# 16-DDR4_ECC_AND_TERMINATIONS.net
KiCad netlist of a schematic drawn in Altium Designer
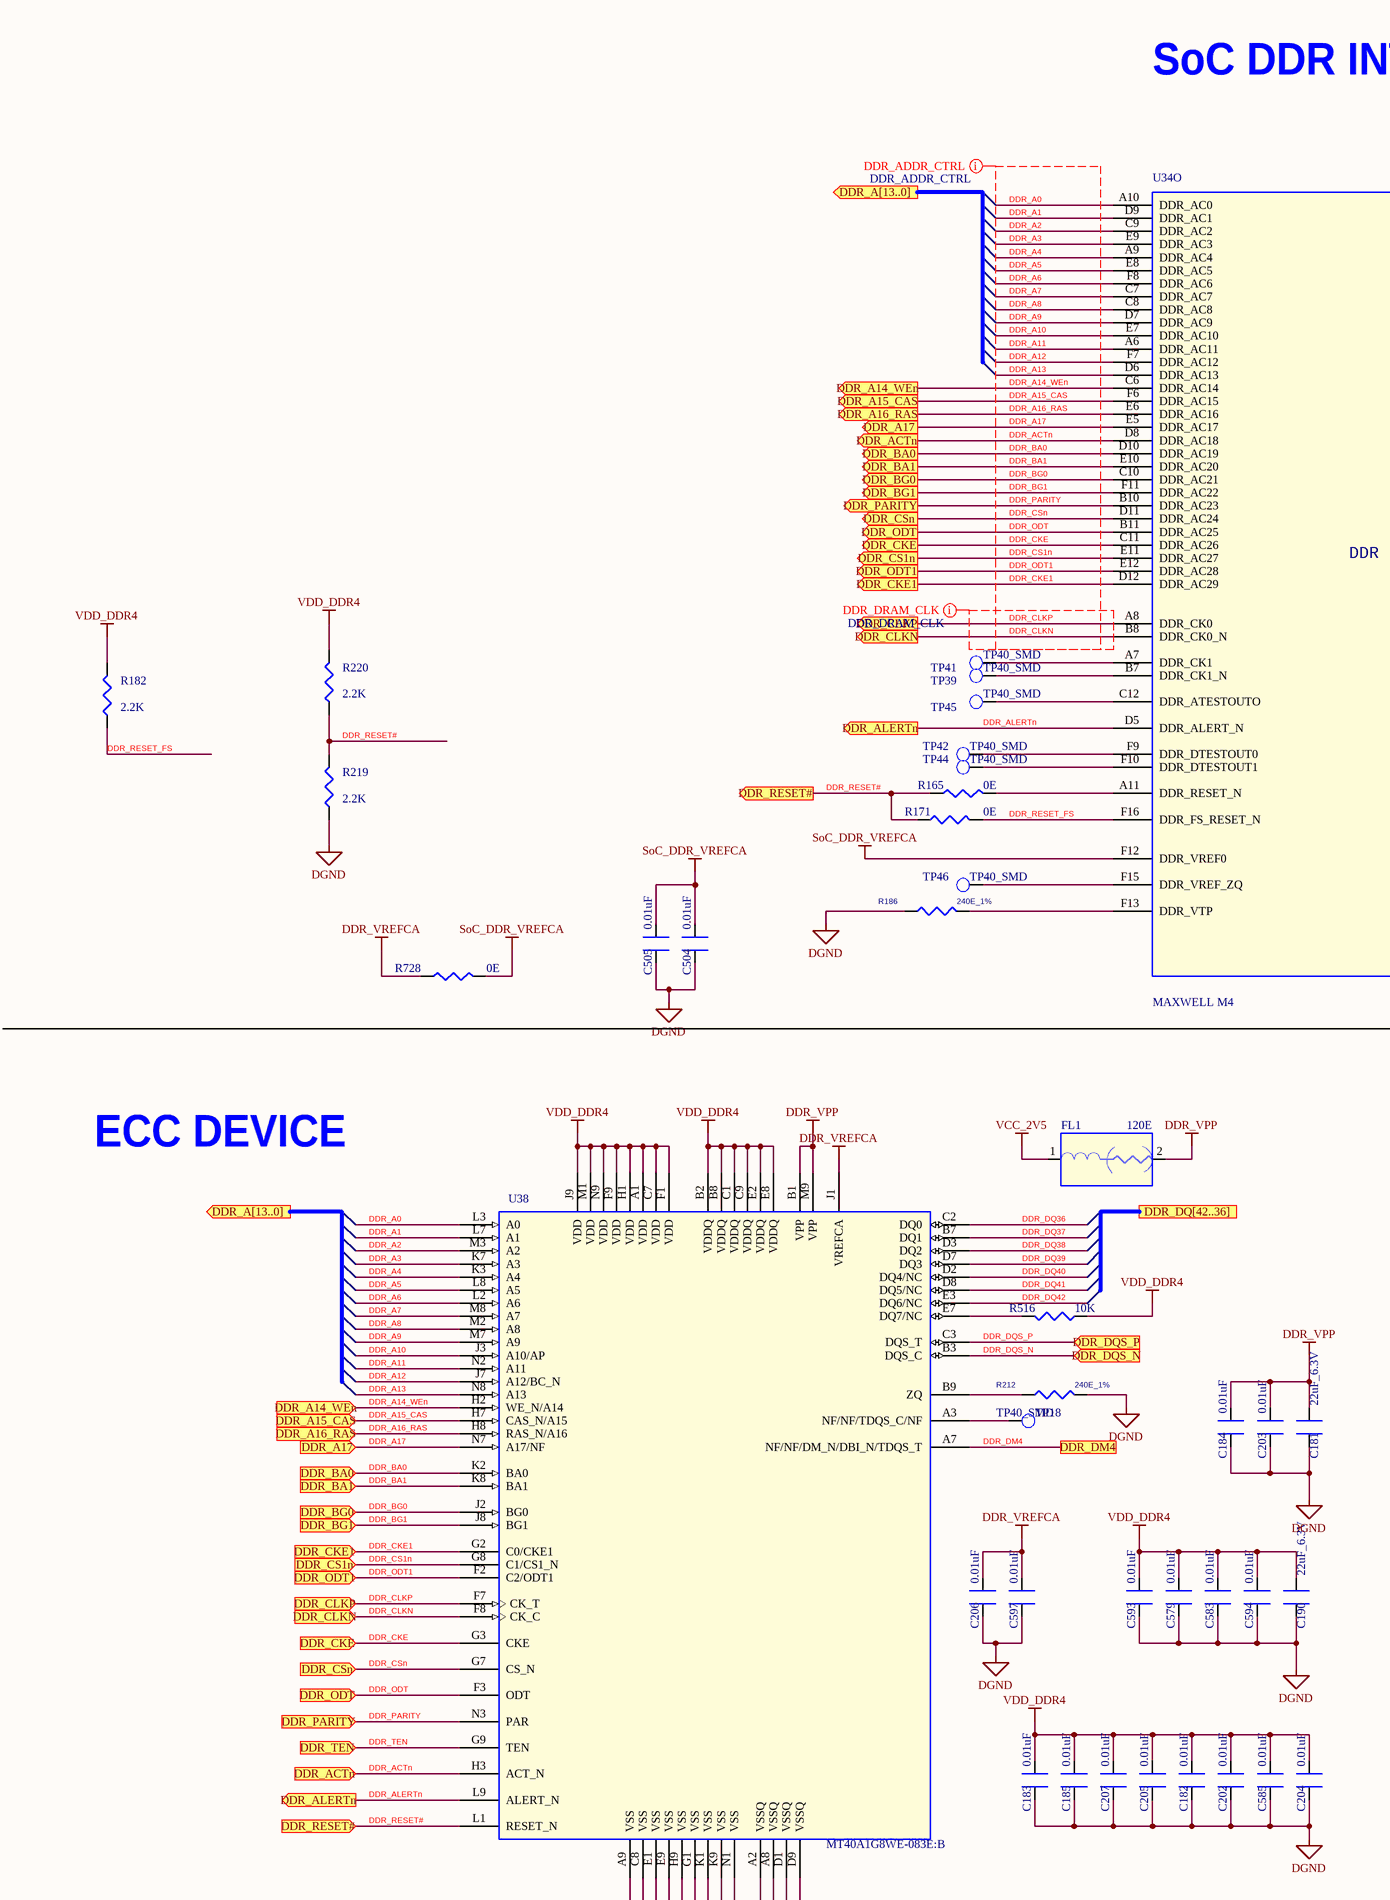
[diagram p0: 16-DDR4 ECC AND TERMINATIONS.SchDoc, top left]
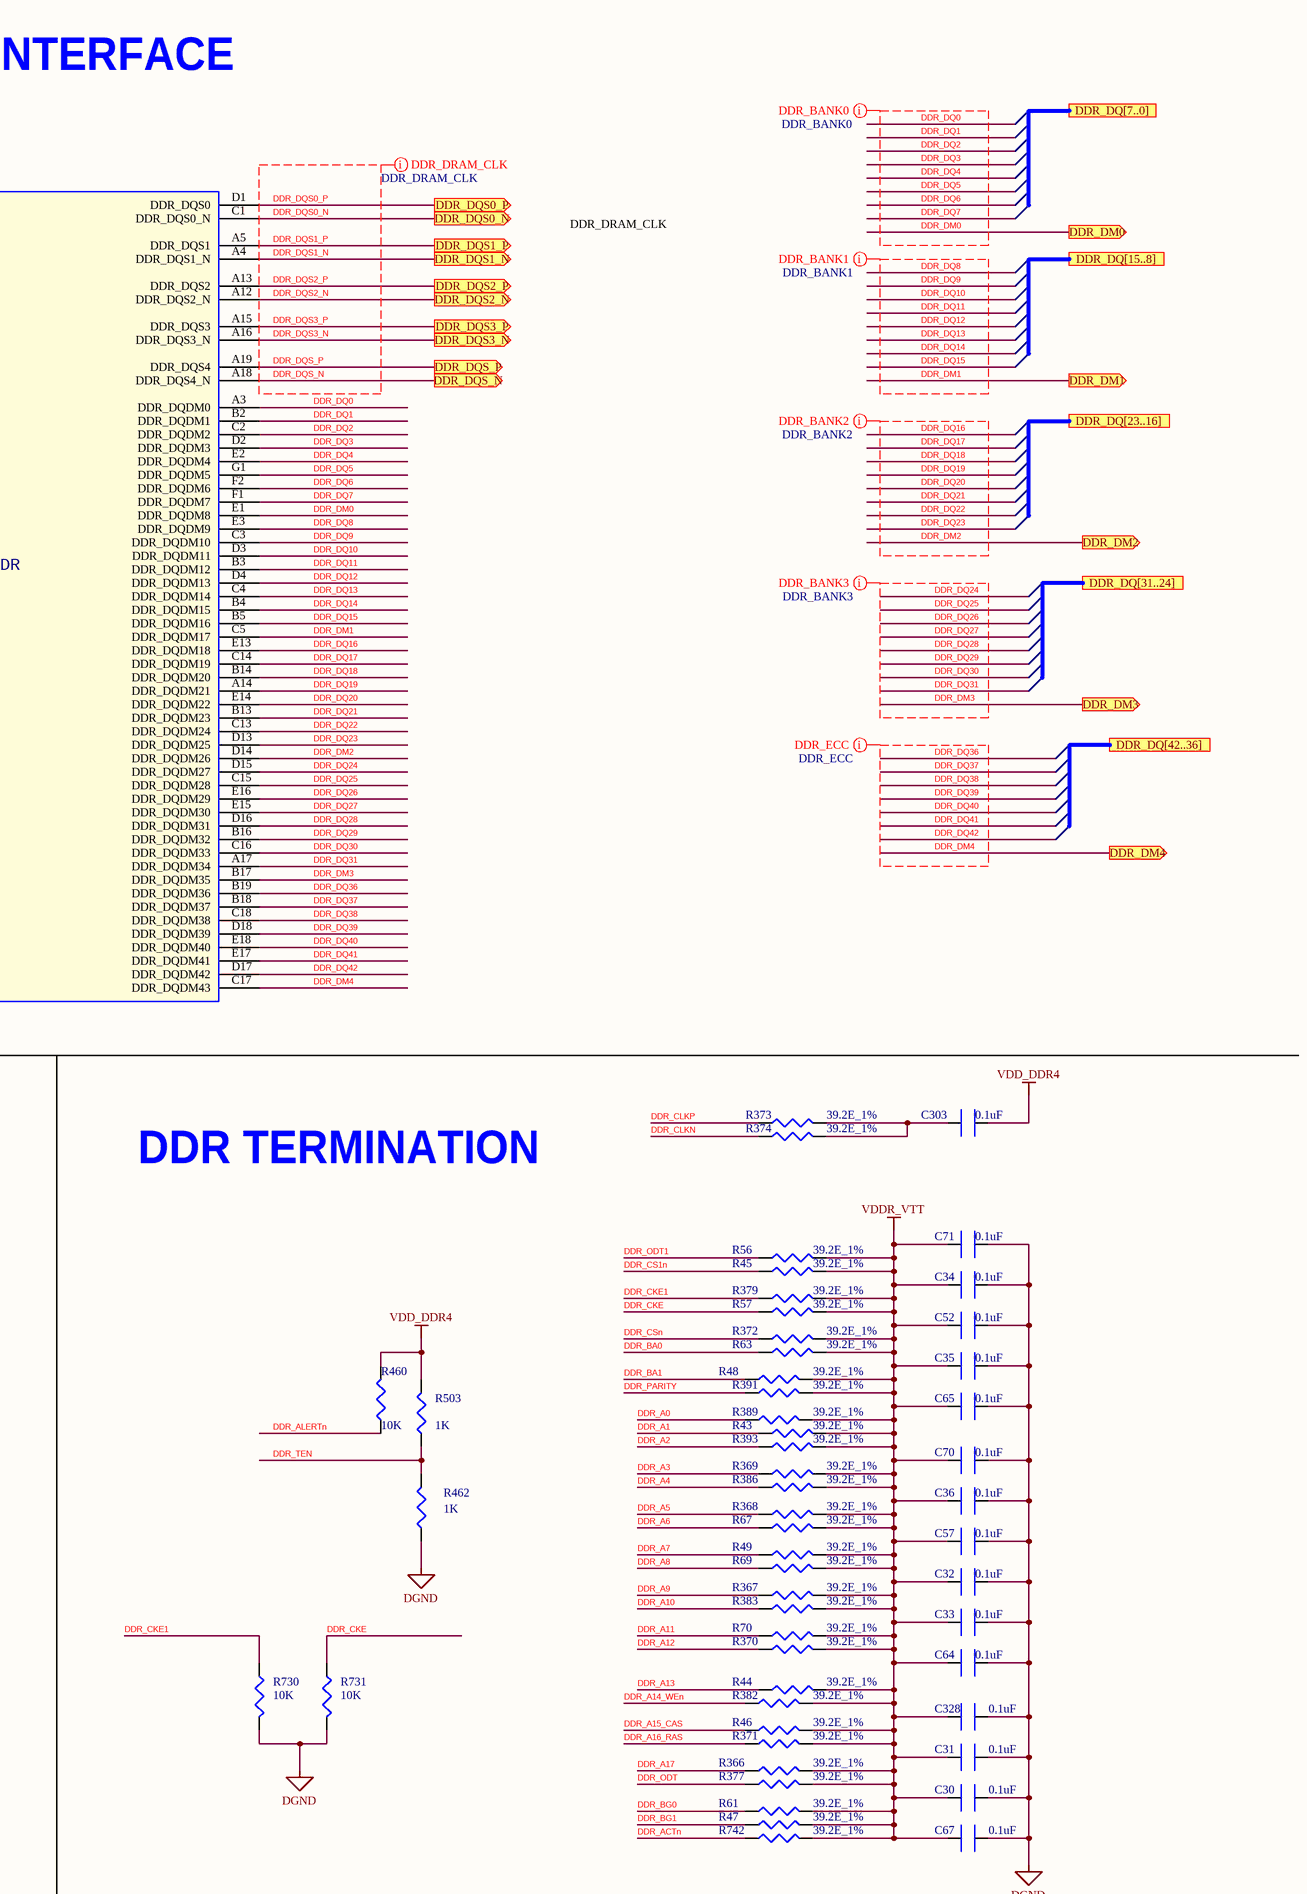
[diagram p1: 16-DDR4 ECC AND TERMINATIONS.SchDoc, top right]
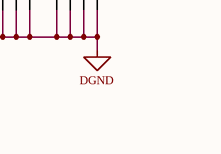
[diagram p2: 16-DDR4 ECC AND TERMINATIONS.SchDoc, bottom left]
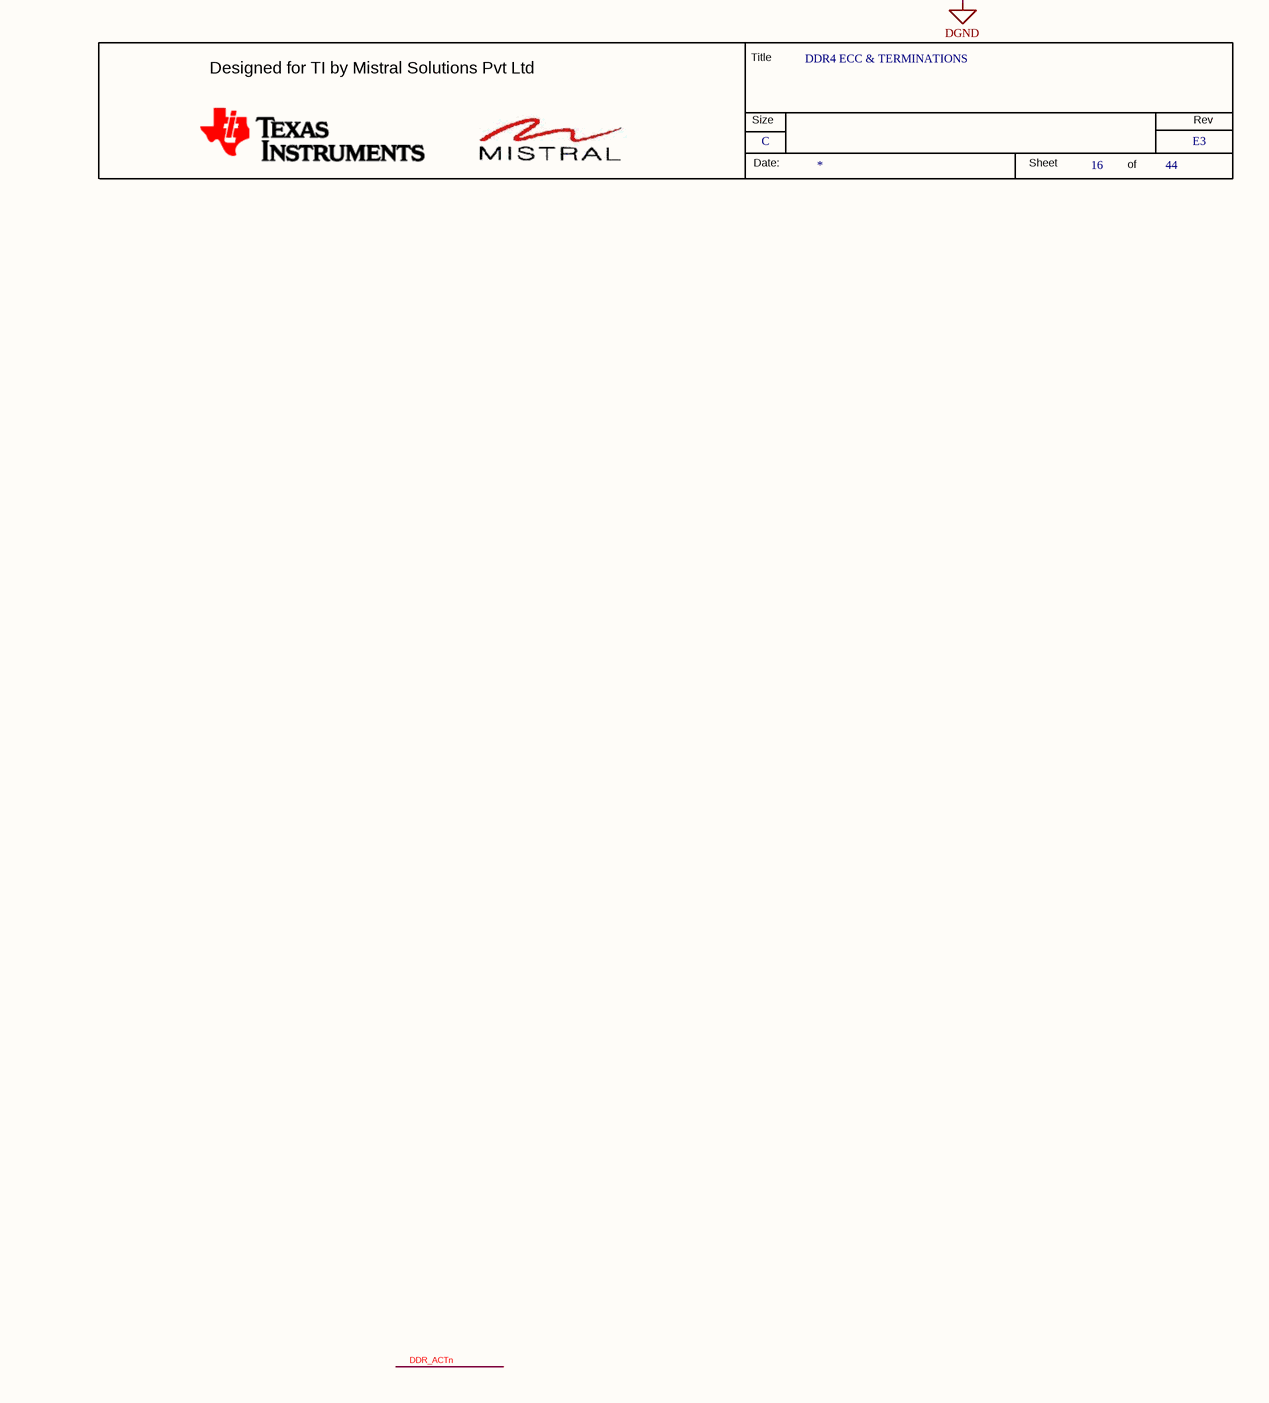
[diagram p3: 16-DDR4 ECC AND TERMINATIONS.SchDoc, bottom right]

(export (version "E")
  (design (tool "Eeschema 10.0.6"))
  (components
    (comp (ref "C30")
      (value "0.1uF")
      (footprint "TMDX654GPEVM_BRD:CAP0201_0-5")
      (description "CAP CERAMIC 0.1uF 16V 10% X5R 0201")
      (fields
        (field (name "MISTRAL PART NO") "120009030072-R")
        (field (name "MFR_PART_NUMBER") "GRM033R61C104KE84J")
      )
      (libsource (lib "*") (part "CAP_Dup3"))
    )
    (comp (ref "C31")
      (value "0.1uF")
      (footprint "TMDX654GPEVM_BRD:CAP0201_0-5")
      (description "CAP CERAMIC 0.1uF 16V 10% X5R 0201")
      (fields (field (name "DISTRIBUTOR_PART_NUMBER") "490-16742-1-ND") (field (name "VOLTAGE") "16V"))
      (libsource (lib "*") (part "CAP_Dup3"))
    )
    (comp (ref "C32")
      (value "0.1uF")
      (footprint "TMDX654GPEVM_BRD:CAP0201_0-5")
      (description "CAP CERAMIC 0.1uF 16V 10% X5R 0201")
      (fields
        (field (name "MISTRAL PART NO") "120009030072-R")
        (field (name "MFR_PART_NUMBER") "GRM033R61C104KE84J")
      )
      (libsource (lib "*") (part "CAP_Dup3"))
    )
    (comp (ref "C33")
      (value "0.1uF")
      (footprint "TMDX654GPEVM_BRD:CAP0201_0-5")
      (description "CAP CERAMIC 0.1uF 16V 10% X5R 0201")
      (fields
        (field (name "MISTRAL PART NO") "120009030072-R")
        (field (name "MFR_PART_NUMBER") "GRM033R61C104KE84J")
      )
      (libsource (lib "*") (part "CAP_Dup3"))
    )
    (comp (ref "C34")
      (value "0.1uF")
      (footprint "TMDX654GPEVM_BRD:CAP0201_0-5")
      (description "CAP CERAMIC 0.1uF 16V 10% X5R 0201")
      (fields
        (field (name "MISTRAL PART NO") "120009030072-R")
        (field (name "MFR_PART_NUMBER") "GRM033R61C104KE84J")
      )
      (libsource (lib "*") (part "CAP_Dup3"))
    )
    (comp (ref "C35")
      (value "0.1uF")
      (footprint "TMDX654GPEVM_BRD:CAP0201_0-5")
      (description "CAP CERAMIC 0.1uF 16V 10% X5R 0201")
      (fields (field (name "DISTRIBUTOR_PART_NUMBER") "490-16742-1-ND") (field (name "VOLTAGE") "16V"))
      (libsource (lib "*") (part "CAP_Dup3"))
    )
    (comp (ref "C36")
      (value "0.1uF")
      (footprint "TMDX654GPEVM_BRD:CAP0201_0-5")
      (description "CAP CERAMIC 0.1uF 16V 10% X5R 0201")
      (fields
        (field (name "MISTRAL PART NO") "120009030072-R")
        (field (name "MFR_PART_NUMBER") "GRM033R61C104KE84J")
      )
      (libsource (lib "*") (part "CAP_Dup3"))
    )
    (comp (ref "C52")
      (value "0.1uF")
      (footprint "TMDX654GPEVM_BRD:CAP0201_0-5")
      (description "CAP CERAMIC 0.1uF 16V 10% X5R 0201")
      (fields
        (field (name "MISTRAL PART NO") "120009030072-R")
        (field (name "MFR_PART_NUMBER") "GRM033R61C104KE84J")
      )
      (libsource (lib "*") (part "CAP_Dup3"))
    )
    (comp (ref "C57")
      (value "0.1uF")
      (footprint "TMDX654GPEVM_BRD:CAP0201_0-5")
      (description "CAP CERAMIC 0.1uF 16V 10% X5R 0201")
      (fields
        (field (name "MISTRAL PART NO") "120009030072-R")
        (field (name "MFR_PART_NUMBER") "GRM033R61C104KE84J")
      )
      (libsource (lib "*") (part "CAP_Dup3"))
    )
    (comp (ref "C64")
      (value "0.1uF")
      (footprint "TMDX654GPEVM_BRD:CAP0201_0-5")
      (description "CAP CERAMIC 0.1uF 16V 10% X5R 0201")
      (fields
        (field (name "MISTRAL PART NO") "120009030072-R")
        (field (name "MFR_PART_NUMBER") "GRM033R61C104KE84J")
      )
      (libsource (lib "*") (part "CAP_Dup3"))
    )
    (comp (ref "C65")
      (value "0.1uF")
      (footprint "TMDX654GPEVM_BRD:CAP0201_0-5")
      (description "CAP CERAMIC 0.1uF 16V 10% X5R 0201")
      (fields
        (field (name "MISTRAL PART NO") "120009030072-R")
        (field (name "MFR_PART_NUMBER") "GRM033R61C104KE84J")
      )
      (libsource (lib "*") (part "CAP_Dup3"))
    )
    (comp (ref "C67")
      (value "0.1uF")
      (footprint "TMDX654GPEVM_BRD:CAP0201_0-5")
      (description "CAP CERAMIC 0.1uF 16V 10% X5R 0201")
      (fields
        (field (name "MISTRAL PART NO") "120009030072-R")
        (field (name "MFR_PART_NUMBER") "GRM033R61C104KE84J")
      )
      (libsource (lib "*") (part "CAP_Dup3"))
    )
    (comp (ref "C70")
      (value "0.1uF")
      (footprint "TMDX654GPEVM_BRD:CAP0201_0-5")
      (description "CAP CERAMIC 0.1uF 16V 10% X5R 0201")
      (fields
        (field (name "MISTRAL PART NO") "120009030072-R")
        (field (name "MFR_PART_NUMBER") "GRM033R61C104KE84J")
      )
      (libsource (lib "*") (part "CAP_Dup3"))
    )
    (comp (ref "C71")
      (value "0.1uF")
      (footprint "TMDX654GPEVM_BRD:CAP0201_0-5")
      (description "CAP CERAMIC 0.1uF 16V 10% X5R 0201")
      (fields
        (field (name "MISTRAL PART NO") "120009030072-R")
        (field (name "MFR_PART_NUMBER") "GRM033R61C104KE84J")
      )
      (libsource (lib "*") (part "CAP_Dup3"))
    )
    (comp (ref "C181")
      (value "22uF_6.3V")
      (footprint "TMDX654GPEVM_BRD:CAP0603")
      (description "CAP CERAMIC 22uF 6.3V 20% X5R 0603")
      (fields
        (field (name "MISTRAL PART NO") "120015090007-R")
        (field (name "MFR_PART_NUMBER") "GRM188R60J226MEA0")
      )
      (libsource (lib "*") (part "CAP_Dup3"))
    )
    (comp (ref "C182")
      (value "0.01uF")
      (footprint "TMDX654GPEVM_BRD:CAP0201_0-5")
      (description "CAP CERAMIC 0.01uF 25V 10% X5R 0201")
      (fields (field (name "DISTRIBUTOR_PART_NUMBER") "GRM033R61E103KA12J-ND") (field (name "VOLTAGE") "25V"))
      (libsource (lib "*") (part "CAP_Dup3"))
    )
    (comp (ref "C183")
      (value "0.01uF")
      (footprint "TMDX654GPEVM_BRD:CAP0201_0-5")
      (description "CAP CERAMIC 0.01uF 25V 10% X5R 0201")
      (fields (field (name "DISTRIBUTOR_PART_NUMBER") "GRM033R61E103KA12J-ND") (field (name "VOLTAGE") "25V"))
      (libsource (lib "*") (part "CAP_Dup3"))
    )
    (comp (ref "C184")
      (value "0.01uF")
      (footprint "TMDX654GPEVM_BRD:CAP0201_0-5")
      (description "CAP CERAMIC 0.01uF 25V 10% X5R 0201")
      (fields (field (name "DISTRIBUTOR_PART_NUMBER") "GRM033R61E103KA12J-ND") (field (name "VOLTAGE") "25V"))
      (libsource (lib "*") (part "CAP_Dup3"))
    )
    (comp (ref "C185")
      (value "0.01uF")
      (footprint "TMDX654GPEVM_BRD:CAP0201_0-5")
      (description "CAP CERAMIC 0.01uF 25V 10% X5R 0201")
      (fields (field (name "DISTRIBUTOR_PART_NUMBER") "GRM033R61E103KA12J-ND") (field (name "VOLTAGE") "25V"))
      (libsource (lib "*") (part "CAP_Dup3"))
    )
    (comp (ref "C190")
      (value "22uF_6.3V")
      (footprint "TMDX654GPEVM_BRD:CAP0603")
      (description "CAP CERAMIC 22uF 6.3V 20% X5R 0603")
      (fields
        (field (name "MISTRAL PART NO") "120015090007-R")
        (field (name "MFR_PART_NUMBER") "GRM188R60J226MEA0")
      )
      (libsource (lib "*") (part "CAP_Dup3"))
    )
    (comp (ref "C202")
      (value "0.01uF")
      (footprint "TMDX654GPEVM_BRD:CAP0201_0-5")
      (description "CAP CERAMIC 0.01uF 25V 10% X5R 0201")
      (fields (field (name "DISTRIBUTOR_PART_NUMBER") "GRM033R61E103KA12J-ND") (field (name "VOLTAGE") "25V"))
      (libsource (lib "*") (part "CAP_Dup3"))
    )
    (comp (ref "C203")
      (value "0.01uF")
      (footprint "TMDX654GPEVM_BRD:CAP0201_0-5")
      (description "CAP CERAMIC 0.01uF 25V 10% X5R 0201")
      (fields (field (name "DISTRIBUTOR_PART_NUMBER") "GRM033R61E103KA12J-ND") (field (name "VOLTAGE") "25V"))
      (libsource (lib "*") (part "CAP_Dup3"))
    )
    (comp (ref "C204")
      (value "0.01uF")
      (footprint "TMDX654GPEVM_BRD:CAP0201_0-5")
      (description "CAP CERAMIC 0.01uF 25V 10% X5R 0201")
      (fields
        (field (name "MISTRAL PART NO") "120018010007-R")
        (field (name "MFR_PART_NUMBER") "GRM033R61E103KA12J")
      )
      (libsource (lib "*") (part "CAP_Dup3"))
    )
    (comp (ref "C205")
      (value "0.01uF")
      (footprint "TMDX654GPEVM_BRD:CAP0201_0-5")
      (description "CAP CERAMIC 0.01uF 25V 10% X5R 0201")
      (fields (field (name "DISTRIBUTOR_PART_NUMBER") "GRM033R61E103KA12J-ND") (field (name "VOLTAGE") "25V"))
      (libsource (lib "*") (part "CAP_Dup3"))
    )
    (comp (ref "C206")
      (value "0.01uF")
      (footprint "TMDX654GPEVM_BRD:CAP0201_0-5")
      (description "CAP CERAMIC 0.01uF 25V 10% X5R 0201")
      (fields (field (name "DISTRIBUTOR_PART_NUMBER") "GRM033R61E103KA12J-ND") (field (name "VOLTAGE") "25V"))
      (libsource (lib "*") (part "CAP_Dup3"))
    )
    (comp (ref "C207")
      (value "0.01uF")
      (footprint "TMDX654GPEVM_BRD:CAP0201_0-5")
      (description "CAP CERAMIC 0.01uF 25V 10% X5R 0201")
      (fields (field (name "DISTRIBUTOR_PART_NUMBER") "GRM033R61E103KA12J-ND") (field (name "VOLTAGE") "25V"))
      (libsource (lib "*") (part "CAP_Dup3"))
    )
    (comp (ref "C303")
      (value "0.1uF")
      (footprint "TMDX654GPEVM_BRD:CAP0201_0-5")
      (description "CAP CERAMIC 0.1uF 16V 10% X5R 0201")
      (fields (field (name "DISTRIBUTOR_PART_NUMBER") "490-16742-1-ND") (field (name "VOLTAGE") "16V"))
      (libsource (lib "*") (part "CAP_Dup3"))
    )
    (comp (ref "C328")
      (value "0.1uF")
      (footprint "TMDX654GPEVM_BRD:CAP0201_0-5")
      (description "CAP CERAMIC 0.1uF 16V 10% X5R 0201")
      (fields
        (field (name "MISTRAL PART NO") "120009030072-R")
        (field (name "MFR_PART_NUMBER") "GRM033R61C104KE84J")
      )
      (libsource (lib "*") (part "CAP_Dup3"))
    )
    (comp (ref "C504")
      (value "0.01uF")
      (footprint "TMDX654GPEVM_BRD:CAP0201_0-5")
      (description "CAP CERAMIC 0.01uF 25V 10% X5R 0201")
      (fields (field (name "DISTRIBUTOR_PART_NUMBER") "GRM033R61E103KA12J-ND") (field (name "VOLTAGE") "25V"))
      (libsource (lib "*") (part "CAP_Dup3"))
    )
    (comp (ref "C505")
      (value "0.01uF")
      (footprint "TMDX654GPEVM_BRD:CAP0201_0-5")
      (description "CAP CERAMIC 0.01uF 25V 10% X5R 0201")
      (fields (field (name "DISTRIBUTOR_PART_NUMBER") "GRM033R61E103KA12J-ND") (field (name "VOLTAGE") "25V"))
      (libsource (lib "*") (part "CAP_Dup3"))
    )
    (comp (ref "C579")
      (value "0.01uF")
      (footprint "TMDX654GPEVM_BRD:CAP0201_0-5")
      (description "CAP CERAMIC 0.01uF 25V 10% X5R 0201")
      (fields (field (name "DISTRIBUTOR_PART_NUMBER") "GRM033R61E103KA12J-ND") (field (name "VOLTAGE") "25V"))
      (libsource (lib "*") (part "CAP_Dup3"))
    )
    (comp (ref "C583")
      (value "0.01uF")
      (footprint "TMDX654GPEVM_BRD:CAP0201_0-5")
      (description "CAP CERAMIC 0.01uF 25V 10% X5R 0201")
      (fields (field (name "DISTRIBUTOR_PART_NUMBER") "GRM033R61E103KA12J-ND") (field (name "VOLTAGE") "25V"))
      (libsource (lib "*") (part "CAP_Dup3"))
    )
    (comp (ref "C585")
      (value "0.01uF")
      (footprint "TMDX654GPEVM_BRD:CAP0201_0-5")
      (description "CAP CERAMIC 0.01uF 25V 10% X5R 0201")
      (fields (field (name "DISTRIBUTOR_PART_NUMBER") "GRM033R61E103KA12J-ND") (field (name "VOLTAGE") "25V"))
      (libsource (lib "*") (part "CAP_Dup3"))
    )
    (comp (ref "C593")
      (value "0.01uF")
      (footprint "TMDX654GPEVM_BRD:CAP0201_0-5")
      (description "CAP CERAMIC 0.01uF 25V 10% X5R 0201")
      (fields (field (name "DISTRIBUTOR_PART_NUMBER") "GRM033R61E103KA12J-ND") (field (name "VOLTAGE") "25V"))
      (libsource (lib "*") (part "CAP_Dup3"))
    )
    (comp (ref "C594")
      (value "0.01uF")
      (footprint "TMDX654GPEVM_BRD:CAP0201_0-5")
      (description "CAP CERAMIC 0.01uF 25V 10% X5R 0201")
      (fields (field (name "DISTRIBUTOR_PART_NUMBER") "GRM033R61E103KA12J-ND") (field (name "VOLTAGE") "25V"))
      (libsource (lib "*") (part "CAP_Dup3"))
    )
    (comp (ref "C597")
      (value "0.01uF")
      (footprint "TMDX654GPEVM_BRD:CAP0201_0-5")
      (description "CAP CERAMIC 0.01uF 25V 10% X5R 0201")
      (fields (field (name "DISTRIBUTOR_PART_NUMBER") "GRM033R61E103KA12J-ND") (field (name "VOLTAGE") "25V"))
      (libsource (lib "*") (part "CAP_Dup3"))
    )
    (comp (ref "FL1")
      (value "120E")
      (footprint "EMIFIL_BLM15A_0402_0-6")
      (description "FERRITE CHIP 120E 1.3A 0402")
      (fields
        (field (name "MISTRAL PART NO") "130012030043-R")
        (field (name "MFR_PART_NUMBER") "BLM15PD121SN1")
      )
      (libsource (lib "*") (part "EMIFILTER_IND"))
    )
    (comp (ref "R43")
      (value "39.2E_1%")
      (footprint "RES0402")
      (description "RES 39.2E 1/16W 1% 0402")
      (fields
        (field (name "MISTRAL PART NO") "110011040030-R")
        (field (name "MFR_PART_NUMBER") "RMCF0402FT39R2")
      )
      (libsource (lib "*") (part "RESISTOR_Dup5"))
    )
    (comp (ref "R44")
      (value "39.2E_1%")
      (footprint "RES0402")
      (description "RES 39.2E 1/16W 1% 0402")
      (fields
        (field (name "MISTRAL PART NO") "110011040030-R")
        (field (name "MFR_PART_NUMBER") "RMCF0402FT39R2")
      )
      (libsource (lib "*") (part "RESISTOR_Dup5"))
    )
    (comp (ref "R45")
      (value "39.2E_1%")
      (footprint "RES0402")
      (description "RES 39.2E 1/16W 1% 0402")
      (fields (field (name "DISTRIBUTOR_PART_NUMBER") "RMCF0402FT39R2CT-ND") (field (name "VOLTAGE") "NA"))
      (libsource (lib "*") (part "RESISTOR_Dup5"))
    )
    (comp (ref "R46")
      (value "39.2E_1%")
      (footprint "RES0402")
      (description "RES 39.2E 1/16W 1% 0402")
      (fields (field (name "DISTRIBUTOR_PART_NUMBER") "RMCF0402FT39R2CT-ND") (field (name "VOLTAGE") "NA"))
      (libsource (lib "*") (part "RESISTOR_Dup5"))
    )
    (comp (ref "R47")
      (value "39.2E_1%")
      (footprint "RES0402")
      (description "RES 39.2E 1/16W 1% 0402")
      (fields
        (field (name "MISTRAL PART NO") "110011040030-R")
        (field (name "MFR_PART_NUMBER") "RMCF0402FT39R2")
      )
      (libsource (lib "*") (part "RESISTOR_Dup5"))
    )
    (comp (ref "R48")
      (value "39.2E_1%")
      (footprint "RES0402")
      (description "RES 39.2E 1/16W 1% 0402")
      (fields (field (name "DISTRIBUTOR_PART_NUMBER") "RMCF0402FT39R2CT-ND") (field (name "VOLTAGE") "NA"))
      (libsource (lib "*") (part "RESISTOR_Dup5"))
    )
    (comp (ref "R49")
      (value "39.2E_1%")
      (footprint "RES0402")
      (description "RES 39.2E 1/16W 1% 0402")
      (fields
        (field (name "MISTRAL PART NO") "110011040030-R")
        (field (name "MFR_PART_NUMBER") "RMCF0402FT39R2")
      )
      (libsource (lib "*") (part "RESISTOR_Dup5"))
    )
    (comp (ref "R56")
      (value "39.2E_1%")
      (footprint "RES0402")
      (description "RES 39.2E 1/16W 1% 0402")
      (fields (field (name "DISTRIBUTOR_PART_NUMBER") "RMCF0402FT39R2CT-ND") (field (name "VOLTAGE") "NA"))
      (libsource (lib "*") (part "RESISTOR_Dup5"))
    )
    (comp (ref "R57")
      (value "39.2E_1%")
      (footprint "RES0402")
      (description "RES 39.2E 1/16W 1% 0402")
      (fields (field (name "DISTRIBUTOR_PART_NUMBER") "RMCF0402FT39R2CT-ND") (field (name "VOLTAGE") "NA"))
      (libsource (lib "*") (part "RESISTOR_Dup5"))
    )
    (comp (ref "R61")
      (value "39.2E_1%")
      (footprint "RES0402")
      (description "RES 39.2E 1/16W 1% 0402")
      (fields (field (name "DISTRIBUTOR_PART_NUMBER") "RMCF0402FT39R2CT-ND") (field (name "VOLTAGE") "NA"))
      (libsource (lib "*") (part "RESISTOR_Dup5"))
    )
    (comp (ref "R63")
      (value "39.2E_1%")
      (footprint "RES0402")
      (description "RES 39.2E 1/16W 1% 0402")
      (fields (field (name "DISTRIBUTOR_PART_NUMBER") "RMCF0402FT39R2CT-ND") (field (name "VOLTAGE") "NA"))
      (libsource (lib "*") (part "RESISTOR_Dup5"))
    )
    (comp (ref "R67")
      (value "39.2E_1%")
      (footprint "RES0402")
      (description "RES 39.2E 1/16W 1% 0402")
      (fields
        (field (name "MISTRAL PART NO") "110011040030-R")
        (field (name "MFR_PART_NUMBER") "RMCF0402FT39R2")
      )
      (libsource (lib "*") (part "RESISTOR_Dup5"))
    )
    (comp (ref "R69")
      (value "39.2E_1%")
      (footprint "RES0402")
      (description "RES 39.2E 1/16W 1% 0402")
      (fields
        (field (name "MISTRAL PART NO") "110011040030-R")
        (field (name "MFR_PART_NUMBER") "RMCF0402FT39R2")
      )
      (libsource (lib "*") (part "RESISTOR_Dup5"))
    )
    (comp (ref "R70")
      (value "39.2E_1%")
      (footprint "RES0402")
      (description "RES 39.2E 1/16W 1% 0402")
      (fields
        (field (name "MISTRAL PART NO") "110011040030-R")
        (field (name "MFR_PART_NUMBER") "RMCF0402FT39R2")
      )
      (libsource (lib "*") (part "RESISTOR_Dup5"))
    )
    (comp (ref "R165")
      (value "0E")
      (footprint "TMDX654GPEVM_BRD:RES0402_0-5")
      (description "RES 0E 1/16W 0402")
      (fields (field (name "VOLTAGE") "NA") (field (name "MISTRAL PART NO") "110010080019-P"))
      (libsource (lib "*") (part "RESISTOR_Dup2"))
    )
    (comp (ref "R171")
      (value "0E")
      (footprint "TMDX654GPEVM_BRD:RES0402_0-5")
      (description "RES 0E 1/16W 0402")
      (fields (field (name "DISTRIBUTOR_PART_NUMBER") "541-0.0JCT-ND") (field (name "TOLERANCE") "NA"))
      (libsource (lib "*") (part "RESISTOR_Dup2"))
    )
    (comp (ref "R182")
      (value "2.2K")
      (footprint "RES0402_0-5")
      (description "RES 2.2K 1/16W 5% 0402")
      (fields (field (name "DISTRIBUTOR_PART_NUMBER") "311-2.2KJRCT-ND") (field (name "VOLTAGE") "NA"))
      (libsource (lib "*") (part "RESISTOR_Dup5"))
    )
    (comp (ref "R186")
      (value "240E_1%")
      (footprint "RES0402")
      (description "RES 240E 1/10W 1% 0402")
      (fields (field (name "DISTRIBUTOR_PART_NUMBER") "P240LCT-ND") (field (name "VOLTAGE") "NA"))
      (libsource (lib "*") (part "RESISTOR_Dup1"))
    )
    (comp (ref "R212")
      (value "240E_1%")
      (footprint "RES0402")
      (description "RES 240E 1/10W 1% 0402")
      (fields
        (field (name "MISTRAL PART NO") "110011060017-R")
        (field (name "MFR_PART_NUMBER") "ERJ-2RKF2400X")
      )
      (libsource (lib "*") (part "RESISTOR_Dup1"))
    )
    (comp (ref "R219")
      (value "2.2K")
      (footprint "RES0402_0-5")
      (description "RES 2.2K 1/16W 5% 0402")
      (fields (field (name "DISTRIBUTOR_PART_NUMBER") "311-2.2KJRCT-ND") (field (name "VOLTAGE") "NA"))
      (libsource (lib "*") (part "RESISTOR_Dup5"))
    )
    (comp (ref "R220")
      (value "2.2K")
      (footprint "RES0402_0-5")
      (description "RES 2.2K 1/16W 5% 0402")
      (fields (field (name "DISTRIBUTOR_PART_NUMBER") "311-2.2KJRCT-ND") (field (name "VOLTAGE") "NA"))
      (libsource (lib "*") (part "RESISTOR_Dup5"))
    )
    (comp (ref "R366")
      (value "39.2E_1%")
      (footprint "RES0402")
      (description "RES 39.2E 1/16W 1% 0402")
      (fields
        (field (name "MISTRAL PART NO") "110011040030-R")
        (field (name "MFR_PART_NUMBER") "RMCF0402FT39R2")
      )
      (libsource (lib "*") (part "RESISTOR_Dup5"))
    )
    (comp (ref "R367")
      (value "39.2E_1%")
      (footprint "RES0402")
      (description "RES 39.2E 1/16W 1% 0402")
      (fields (field (name "DISTRIBUTOR_PART_NUMBER") "RMCF0402FT39R2CT-ND") (field (name "VOLTAGE") "NA"))
      (libsource (lib "*") (part "RESISTOR_Dup5"))
    )
    (comp (ref "R368")
      (value "39.2E_1%")
      (footprint "RES0402")
      (description "RES 39.2E 1/16W 1% 0402")
      (fields
        (field (name "MISTRAL PART NO") "110011040030-R")
        (field (name "MFR_PART_NUMBER") "RMCF0402FT39R2")
      )
      (libsource (lib "*") (part "RESISTOR_Dup5"))
    )
    (comp (ref "R369")
      (value "39.2E_1%")
      (footprint "RES0402")
      (description "RES 39.2E 1/16W 1% 0402")
      (fields
        (field (name "MISTRAL PART NO") "110011040030-R")
        (field (name "MFR_PART_NUMBER") "RMCF0402FT39R2")
      )
      (libsource (lib "*") (part "RESISTOR_Dup5"))
    )
    (comp (ref "R370")
      (value "39.2E_1%")
      (footprint "RES0402")
      (description "RES 39.2E 1/16W 1% 0402")
      (fields
        (field (name "MISTRAL PART NO") "110011040030-R")
        (field (name "MFR_PART_NUMBER") "RMCF0402FT39R2")
      )
      (libsource (lib "*") (part "RESISTOR_Dup5"))
    )
    (comp (ref "R371")
      (value "39.2E_1%")
      (footprint "RES0402")
      (description "RES 39.2E 1/16W 1% 0402")
      (fields
        (field (name "MISTRAL PART NO") "110011040030-R")
        (field (name "MFR_PART_NUMBER") "RMCF0402FT39R2")
      )
      (libsource (lib "*") (part "RESISTOR_Dup5"))
    )
    (comp (ref "R372")
      (value "39.2E_1%")
      (footprint "RES0402")
      (description "RES 39.2E 1/16W 1% 0402")
      (fields (field (name "DISTRIBUTOR_PART_NUMBER") "RMCF0402FT39R2CT-ND") (field (name "VOLTAGE") "NA"))
      (libsource (lib "*") (part "RESISTOR_Dup5"))
    )
    (comp (ref "R373")
      (value "39.2E_1%")
      (footprint "RES0402")
      (description "RES 39.2E 1/16W 1% 0402")
      (fields (field (name "DISTRIBUTOR_PART_NUMBER") "RMCF0402FT39R2CT-ND") (field (name "VOLTAGE") "NA"))
      (libsource (lib "*") (part "RESISTOR_Dup5"))
    )
    (comp (ref "R374")
      (value "39.2E_1%")
      (footprint "RES0402")
      (description "RES 39.2E 1/16W 1% 0402")
      (fields (field (name "DISTRIBUTOR_PART_NUMBER") "RMCF0402FT39R2CT-ND") (field (name "VOLTAGE") "NA"))
      (libsource (lib "*") (part "RESISTOR_Dup5"))
    )
    (comp (ref "R377")
      (value "39.2E_1%")
      (footprint "RES0402")
      (description "RES 39.2E 1/16W 1% 0402")
      (fields
        (field (name "MISTRAL PART NO") "110011040030-R")
        (field (name "MFR_PART_NUMBER") "RMCF0402FT39R2")
      )
      (libsource (lib "*") (part "RESISTOR_Dup5"))
    )
    (comp (ref "R379")
      (value "39.2E_1%")
      (footprint "RES0402")
      (description "RES 39.2E 1/16W 1% 0402")
      (fields (field (name "DISTRIBUTOR_PART_NUMBER") "RMCF0402FT39R2CT-ND") (field (name "VOLTAGE") "NA"))
      (libsource (lib "*") (part "RESISTOR_Dup5"))
    )
    (comp (ref "R382")
      (value "39.2E_1%")
      (footprint "RES0402")
      (description "RES 39.2E 1/16W 1% 0402")
      (fields
        (field (name "MISTRAL PART NO") "110011040030-R")
        (field (name "MFR_PART_NUMBER") "RMCF0402FT39R2")
      )
      (libsource (lib "*") (part "RESISTOR_Dup5"))
    )
    (comp (ref "R383")
      (value "39.2E_1%")
      (footprint "RES0402")
      (description "RES 39.2E 1/16W 1% 0402")
      (fields (field (name "DISTRIBUTOR_PART_NUMBER") "RMCF0402FT39R2CT-ND") (field (name "VOLTAGE") "NA"))
      (libsource (lib "*") (part "RESISTOR_Dup5"))
    )
    (comp (ref "R386")
      (value "39.2E_1%")
      (footprint "RES0402")
      (description "RES 39.2E 1/16W 1% 0402")
      (fields
        (field (name "MISTRAL PART NO") "110011040030-R")
        (field (name "MFR_PART_NUMBER") "RMCF0402FT39R2")
      )
      (libsource (lib "*") (part "RESISTOR_Dup5"))
    )
    (comp (ref "R389")
      (value "39.2E_1%")
      (footprint "RES0402")
      (description "RES 39.2E 1/16W 1% 0402")
      (fields (field (name "DISTRIBUTOR_PART_NUMBER") "RMCF0402FT39R2CT-ND") (field (name "VOLTAGE") "NA"))
      (libsource (lib "*") (part "RESISTOR_Dup5"))
    )
    (comp (ref "R391")
      (value "39.2E_1%")
      (footprint "RES0402")
      (description "RES 39.2E 1/16W 1% 0402")
      (fields
        (field (name "MISTRAL PART NO") "110011040030-R")
        (field (name "MFR_PART_NUMBER") "RMCF0402FT39R2")
      )
      (libsource (lib "*") (part "RESISTOR_Dup5"))
    )
    (comp (ref "R393")
      (value "39.2E_1%")
      (footprint "RES0402")
      (description "RES 39.2E 1/16W 1% 0402")
      (fields
        (field (name "MISTRAL PART NO") "110011040030-R")
        (field (name "MFR_PART_NUMBER") "RMCF0402FT39R2")
      )
      (libsource (lib "*") (part "RESISTOR_Dup5"))
    )
    (comp (ref "R460")
      (value "10K")
      (footprint "RES0402_0-5")
      (description "RES 10K 1/16W 5% 0402")
      (fields
        (field (name "MISTRAL PART NO") "110009030208-R")
        (field (name "MFR_PART_NUMBER") "RC0402JR-0710KL")
      )
      (libsource (lib "*") (part "RESISTOR_Dup5"))
    )
    (comp (ref "R462")
      (value "1K")
      (footprint "RES0201")
      (description "RES 1K 1/20W 5% 0201")
      (fields
        (field (name "MISTRAL PART NO") "110015080014-R")
        (field (name "MFR_PART_NUMBER") "CRCW02011K00FKED")
      )
      (libsource (lib "*") (part "RESISTOR_Dup4"))
    )
    (comp (ref "R503")
      (value "1K")
      (footprint "RES0201")
      (description "RES 1K 1/20W 5% 0201")
      (fields
        (field (name "MISTRAL PART NO") "110015080014-R")
        (field (name "MFR_PART_NUMBER") "CRCW02011K00FKED")
      )
      (libsource (lib "*") (part "RESISTOR_Dup4"))
    )
    (comp (ref "R516")
      (value "10K")
      (footprint "RES0402_0-5")
      (description "RES 10K 1/16W 5% 0402")
      (fields (field (name "DISTRIBUTOR_PART_NUMBER") "311-10KJRCT-ND") (field (name "VOLTAGE") "NA"))
      (libsource (lib "*") (part "RESISTOR_Dup5"))
    )
    (comp (ref "R728")
      (value "0E")
      (footprint "RES0402_0-5")
      (description "RES 0E 1/16W 0402")
      (fields
        (field (name "MISTRAL PART NO") "110010080019-P")
        (field (name "MFR_PART_NUMBER") "CRCW04020000Z0ED")
      )
      (libsource (lib "*") (part "RESISTOR_Dup5"))
    )
    (comp (ref "R730")
      (value "10K")
      (footprint "RES0402_0-5")
      (description "RES 10K 1/16W 5% 0402")
      (fields
        (field (name "MISTRAL PART NO") "110009030208-R")
        (field (name "MFR_PART_NUMBER") "RC0402JR-0710KL")
      )
      (libsource (lib "*") (part "RESISTOR_Dup5"))
    )
    (comp (ref "R731")
      (value "10K")
      (footprint "RES0402_0-5")
      (description "RES 10K 1/16W 5% 0402")
      (fields
        (field (name "MISTRAL PART NO") "110009030208-R")
        (field (name "MFR_PART_NUMBER") "RC0402JR-0710KL")
      )
      (libsource (lib "*") (part "RESISTOR_Dup5"))
    )
    (comp (ref "R742")
      (value "39.2E_1%")
      (footprint "RES0402")
      (description "RES 39.2E 1/16W 1% 0402")
      (fields (field (name "DISTRIBUTOR_PART_NUMBER") "RMCF0402FT39R2CT-ND") (field (name "VOLTAGE") "NA"))
      (libsource (lib "*") (part "RESISTOR_Dup5"))
    )
    (comp (ref "TP18")
      (value "TP40_SMD")
      (footprint "TP40_SMD")
      (description "TESTPOINT CIR 40 SMD")
      (fields (field (name "VOLTAGE") "NA") (field (name "MISTRAL PART NO") "130009030933"))
      (libsource (lib "*") (part "TESTPOINT"))
    )
    (comp (ref "TP39")
      (value "TP40_SMD")
      (footprint "TP40_SMD")
      (description "TESTPOINT CIR 40 SMD")
      (fields (field (name "VOLTAGE") "NA") (field (name "MISTRAL PART NO") "130009030933"))
      (libsource (lib "*") (part "TESTPOINT"))
    )
    (comp (ref "TP41")
      (value "TP40_SMD")
      (footprint "TP40_SMD")
      (description "TESTPOINT CIR 40 SMD")
      (fields (field (name "VOLTAGE") "NA") (field (name "MISTRAL PART NO") "130009030933"))
      (libsource (lib "*") (part "TESTPOINT"))
    )
    (comp (ref "TP42")
      (value "TP40_SMD")
      (footprint "TP40_SMD")
      (description "TESTPOINT CIR 40 SMD")
      (fields (field (name "VOLTAGE") "NA") (field (name "MISTRAL PART NO") "130009030933"))
      (libsource (lib "*") (part "TESTPOINT"))
    )
    (comp (ref "TP44")
      (value "TP40_SMD")
      (footprint "TP40_SMD")
      (description "TESTPOINT CIR 40 SMD")
      (fields (field (name "VOLTAGE") "NA") (field (name "MISTRAL PART NO") "130009030933"))
      (libsource (lib "*") (part "TESTPOINT"))
    )
    (comp (ref "TP45")
      (value "TP40_SMD")
      (footprint "TP40_SMD")
      (description "TESTPOINT CIR 40 SMD")
      (fields (field (name "VOLTAGE") "NA") (field (name "MISTRAL PART NO") "130009030933"))
      (libsource (lib "*") (part "TESTPOINT"))
    )
    (comp (ref "TP46")
      (value "TP40_SMD")
      (footprint "TP40_SMD")
      (description "TESTPOINT CIR 40 SMD")
      (fields (field (name "VOLTAGE") "NA") (field (name "MISTRAL PART NO") "130009030933"))
      (libsource (lib "*") (part "TESTPOINT"))
    )
    (comp (ref "U34")
      (value "MAXWELL M4")
      (footprint "BGA784_31-49_910X910_1-7")
      (description "IC MAXWELL MICRO CONTROLLER UNIT BGA784")
      (fields
        (field (name "MISTRAL PART NO") "141217100003")
        (field (name "MFR_PART_NUMBER") "MAXWELL M4_EVM")
      )
      (libsource (lib "*") (part "AM654X_BGA784"))
    )
    (comp (ref "U38")
      (value "MT40A1G8WE-083E:B")
      (footprint "FBGA78_31-49_320X480_1-2")
      (description "IC 1G8 DDR4 SDRAM MEMORY FBGA78")
      (fields (field (name "MISTRAL PART NO") "141117080006-R") (field (name "TOLERANCE") "NA"))
      (libsource (lib "*") (part "MT40A1G8WE-083_FBGA78"))
    )
  )
  (nets
    (net (code "1") (name "/DDR_A0") (class "Default")
      (node (ref "R389") (pin "1") (pinfunction "1_1") (pintype "passive"))
      (node (ref "U34") (pin "A10") (pinfunction "DDR_AC0_A10") (pintype "passive"))
      (node (ref "U38") (pin "L3") (pinfunction "A0_L3") (pintype "input"))
    )
    (net (code "2") (name "/DDR_A1") (class "Default")
      (node (ref "R43") (pin "1") (pinfunction "1_1") (pintype "passive"))
      (node (ref "U34") (pin "D9") (pinfunction "DDR_AC1_D9") (pintype "passive"))
      (node (ref "U38") (pin "L7") (pinfunction "A1_L7") (pintype "input"))
    )
    (net (code "3") (name "/DDR_A2") (class "Default")
      (node (ref "R393") (pin "1") (pinfunction "1_1") (pintype "passive"))
      (node (ref "U34") (pin "C9") (pinfunction "DDR_AC2_C9") (pintype "passive"))
      (node (ref "U38") (pin "M3") (pinfunction "A2_M3") (pintype "input"))
    )
    (net (code "4") (name "/DDR_A3") (class "Default")
      (node (ref "R369") (pin "1") (pinfunction "1_1") (pintype "passive"))
      (node (ref "U34") (pin "E9") (pinfunction "DDR_AC3_E9") (pintype "passive"))
      (node (ref "U38") (pin "K7") (pinfunction "A3_K7") (pintype "input"))
    )
    (net (code "5") (name "/DDR_A4") (class "Default")
      (node (ref "R386") (pin "1") (pinfunction "1_1") (pintype "passive"))
      (node (ref "U34") (pin "A9") (pinfunction "DDR_AC4_A9") (pintype "passive"))
      (node (ref "U38") (pin "K3") (pinfunction "A4_K3") (pintype "input"))
    )
    (net (code "6") (name "/DDR_A5") (class "Default")
      (node (ref "R368") (pin "1") (pinfunction "1_1") (pintype "passive"))
      (node (ref "U34") (pin "E8") (pinfunction "DDR_AC5_E8") (pintype "passive"))
      (node (ref "U38") (pin "L8") (pinfunction "A5_L8") (pintype "input"))
    )
    (net (code "7") (name "/DDR_A6") (class "Default")
      (node (ref "R67") (pin "1") (pinfunction "1_1") (pintype "passive"))
      (node (ref "U34") (pin "F8") (pinfunction "DDR_AC6_F8") (pintype "passive"))
      (node (ref "U38") (pin "L2") (pinfunction "A6_L2") (pintype "input"))
    )
    (net (code "8") (name "/DDR_A7") (class "Default")
      (node (ref "R49") (pin "1") (pinfunction "1_1") (pintype "passive"))
      (node (ref "U34") (pin "C7") (pinfunction "DDR_AC7_C7") (pintype "passive"))
      (node (ref "U38") (pin "M8") (pinfunction "A7_M8") (pintype "input"))
    )
    (net (code "9") (name "/DDR_A8") (class "Default")
      (node (ref "R69") (pin "1") (pinfunction "1_1") (pintype "passive"))
      (node (ref "U34") (pin "C8") (pinfunction "DDR_AC8_C8") (pintype "passive"))
      (node (ref "U38") (pin "M2") (pinfunction "A8_M2") (pintype "input"))
    )
    (net (code "10") (name "/DDR_A9") (class "Default")
      (node (ref "R367") (pin "1") (pinfunction "1_1") (pintype "passive"))
      (node (ref "U34") (pin "D7") (pinfunction "DDR_AC9_D7") (pintype "passive"))
      (node (ref "U38") (pin "M7") (pinfunction "A9_M7") (pintype "input"))
    )
    (net (code "11") (name "/DDR_A10") (class "Default")
      (node (ref "R383") (pin "1") (pinfunction "1_1") (pintype "passive"))
      (node (ref "U34") (pin "E7") (pinfunction "DDR_AC10_E7") (pintype "passive"))
      (node (ref "U38") (pin "J3") (pinfunction "A10/AP_J3") (pintype "input"))
    )
    (net (code "12") (name "/DDR_A11") (class "Default")
      (node (ref "R70") (pin "1") (pinfunction "1_1") (pintype "passive"))
      (node (ref "U34") (pin "A6") (pinfunction "DDR_AC11_A6") (pintype "passive"))
      (node (ref "U38") (pin "N2") (pinfunction "A11_N2") (pintype "input"))
    )
    (net (code "13") (name "/DDR_A12") (class "Default")
      (node (ref "R370") (pin "1") (pinfunction "1_1") (pintype "passive"))
      (node (ref "U34") (pin "F7") (pinfunction "DDR_AC12_F7") (pintype "passive"))
      (node (ref "U38") (pin "J7") (pinfunction "A12/BC_N_J7") (pintype "input"))
    )
    (net (code "14") (name "/DDR_A13") (class "Default")
      (node (ref "R44") (pin "1") (pinfunction "1_1") (pintype "passive"))
      (node (ref "U34") (pin "D6") (pinfunction "DDR_AC13_D6") (pintype "passive"))
      (node (ref "U38") (pin "N8") (pinfunction "A13_N8") (pintype "input"))
    )
    (net (code "15") (name "/DDR_A14_WEn") (class "Default")
      (node (ref "R382") (pin "1") (pinfunction "1_1") (pintype "passive"))
      (node (ref "U34") (pin "C6") (pinfunction "DDR_AC14_C6") (pintype "passive"))
      (node (ref "U38") (pin "H2") (pinfunction "WE_N/A14_H2") (pintype "input"))
    )
    (net (code "16") (name "/DDR_A15_CAS") (class "Default")
      (node (ref "R46") (pin "1") (pinfunction "1_1") (pintype "passive"))
      (node (ref "U34") (pin "F6") (pinfunction "DDR_AC15_F6") (pintype "passive"))
      (node (ref "U38") (pin "H7") (pinfunction "CAS_N/A15_H7") (pintype "input"))
    )
    (net (code "17") (name "/DDR_A16_RAS") (class "Default")
      (node (ref "R371") (pin "1") (pinfunction "1_1") (pintype "passive"))
      (node (ref "U34") (pin "E6") (pinfunction "DDR_AC16_E6") (pintype "passive"))
      (node (ref "U38") (pin "H8") (pinfunction "RAS_N/A16_H8") (pintype "input"))
    )
    (net (code "18") (name "/DDR_A17") (class "Default")
      (node (ref "R366") (pin "1") (pinfunction "1_1") (pintype "passive"))
      (node (ref "U34") (pin "E5") (pinfunction "DDR_AC17_E5") (pintype "passive"))
      (node (ref "U38") (pin "N7") (pinfunction "A17/NF_N7") (pintype "input"))
    )
    (net (code "19") (name "/DDR_ACTn") (class "Default")
      (node (ref "R742") (pin "1") (pinfunction "1_1") (pintype "passive"))
      (node (ref "U34") (pin "D8") (pinfunction "DDR_AC18_D8") (pintype "passive"))
      (node (ref "U38") (pin "H3") (pinfunction "ACT_N_H3") (pintype "passive"))
    )
    (net (code "20") (name "/DDR_ALERTn") (class "Default")
      (node (ref "R460") (pin "1") (pinfunction "1_1") (pintype "passive"))
      (node (ref "U34") (pin "D5") (pinfunction "DDR_ALERT_N_D5") (pintype "passive"))
      (node (ref "U38") (pin "L9") (pinfunction "ALERT_N_L9") (pintype "passive"))
    )
    (net (code "22") (name "/DDR_BA0") (class "Default")
      (node (ref "R63") (pin "1") (pinfunction "1_1") (pintype "passive"))
      (node (ref "U34") (pin "D10") (pinfunction "DDR_AC19_D10") (pintype "passive"))
      (node (ref "U38") (pin "K2") (pinfunction "BA0_K2") (pintype "input"))
    )
    (net (code "23") (name "/DDR_BA1") (class "Default")
      (node (ref "R48") (pin "1") (pinfunction "1_1") (pintype "passive"))
      (node (ref "U34") (pin "E10") (pinfunction "DDR_AC20_E10") (pintype "passive"))
      (node (ref "U38") (pin "K8") (pinfunction "BA1_K8") (pintype "input"))
    )
    (net (code "24") (name "/DDR_BG0") (class "Default")
      (node (ref "R61") (pin "1") (pinfunction "1_1") (pintype "passive"))
      (node (ref "U34") (pin "C10") (pinfunction "DDR_AC21_C10") (pintype "passive"))
      (node (ref "U38") (pin "J2") (pinfunction "BG0_J2") (pintype "input"))
    )
    (net (code "25") (name "/DDR_BG1") (class "Default")
      (node (ref "R47") (pin "1") (pinfunction "1_1") (pintype "passive"))
      (node (ref "U34") (pin "F11") (pinfunction "DDR_AC22_F11") (pintype "passive"))
      (node (ref "U38") (pin "J8") (pinfunction "BG1_J8") (pintype "input"))
    )
    (net (code "26") (name "/DDR_CKE") (class "Default")
      (node (ref "R57") (pin "1") (pinfunction "1_1") (pintype "passive"))
      (node (ref "R731") (pin "1") (pinfunction "1_1") (pintype "passive"))
      (node (ref "U34") (pin "C11") (pinfunction "DDR_AC26_C11") (pintype "passive"))
      (node (ref "U38") (pin "G3") (pinfunction "CKE_G3") (pintype "passive"))
    )
    (net (code "27") (name "/DDR_CKE1") (class "Default")
      (node (ref "R379") (pin "1") (pinfunction "1_1") (pintype "passive"))
      (node (ref "R730") (pin "1") (pinfunction "1_1") (pintype "passive"))
      (node (ref "U34") (pin "D12") (pinfunction "DDR_AC29_D12") (pintype "passive"))
      (node (ref "U38") (pin "G2") (pinfunction "C0/CKE1_G2") (pintype "passive"))
    )
    (net (code "28") (name "/DDR_CLKN") (class "Default")
      (node (ref "R374") (pin "1") (pinfunction "1_1") (pintype "passive"))
      (node (ref "U34") (pin "B8") (pinfunction "DDR_CK0_N_B8") (pintype "passive"))
      (node (ref "U38") (pin "F8") (pinfunction "CK_C_F8") (pintype "input"))
    )
    (net (code "29") (name "/DDR_CLKP") (class "Default")
      (node (ref "R373") (pin "1") (pinfunction "1_1") (pintype "passive"))
      (node (ref "U34") (pin "A8") (pinfunction "DDR_CK0_A8") (pintype "passive"))
      (node (ref "U38") (pin "F7") (pinfunction "CK_T_F7") (pintype "input"))
    )
    (net (code "30") (name "/DDR_CS1n") (class "Default")
      (node (ref "R45") (pin "1") (pinfunction "1_1") (pintype "passive"))
      (node (ref "U34") (pin "E11") (pinfunction "DDR_AC27_E11") (pintype "passive"))
      (node (ref "U38") (pin "G8") (pinfunction "C1/CS1_N_G8") (pintype "passive"))
    )
    (net (code "31") (name "/DDR_CSn") (class "Default")
      (node (ref "R372") (pin "1") (pinfunction "1_1") (pintype "passive"))
      (node (ref "U34") (pin "D11") (pinfunction "DDR_AC24_D11") (pintype "passive"))
      (node (ref "U38") (pin "G7") (pinfunction "CS_N_G7") (pintype "passive"))
    )
    (net (code "32") (name "/DDR_DM0") (class "Default")
      (node (ref "U34") (pin "E1") (pinfunction "DDR_DQDM8_E1") (pintype "passive"))
    )
    (net (code "33") (name "/DDR_DM1") (class "Default")
      (node (ref "U34") (pin "C5") (pinfunction "DDR_DQDM17_C5") (pintype "passive"))
    )
    (net (code "34") (name "/DDR_DM2") (class "Default")
      (node (ref "U34") (pin "D14") (pinfunction "DDR_DQDM26_D14") (pintype "passive"))
    )
    (net (code "35") (name "/DDR_DM3") (class "Default")
      (node (ref "U34") (pin "B17") (pinfunction "DDR_DQDM35_B17") (pintype "passive"))
    )
    (net (code "36") (name "/DDR_DM4") (class "Default")
      (node (ref "U34") (pin "C17") (pinfunction "DDR_DQDM43_C17") (pintype "passive"))
      (node (ref "U38") (pin "A7") (pinfunction "NF/NF/DM_N/DBI_N/TDQS_T_A7") (pintype "passive"))
    )
    (net (code "37") (name "/DDR_DQ0") (class "Default")
      (node (ref "U34") (pin "A3") (pinfunction "DDR_DQDM0_A3") (pintype "passive"))
    )
    (net (code "38") (name "/DDR_DQ1") (class "Default")
      (node (ref "U34") (pin "B2") (pinfunction "DDR_DQDM1_B2") (pintype "passive"))
    )
    (net (code "39") (name "/DDR_DQ2") (class "Default")
      (node (ref "U34") (pin "C2") (pinfunction "DDR_DQDM2_C2") (pintype "passive"))
    )
    (net (code "40") (name "/DDR_DQ3") (class "Default")
      (node (ref "U34") (pin "D2") (pinfunction "DDR_DQDM3_D2") (pintype "passive"))
    )
    (net (code "41") (name "/DDR_DQ4") (class "Default")
      (node (ref "U34") (pin "E2") (pinfunction "DDR_DQDM4_E2") (pintype "passive"))
    )
    (net (code "42") (name "/DDR_DQ5") (class "Default")
      (node (ref "U34") (pin "G1") (pinfunction "DDR_DQDM5_G1") (pintype "passive"))
    )
    (net (code "43") (name "/DDR_DQ6") (class "Default")
      (node (ref "U34") (pin "F2") (pinfunction "DDR_DQDM6_F2") (pintype "passive"))
    )
    (net (code "44") (name "/DDR_DQ7") (class "Default")
      (node (ref "U34") (pin "F1") (pinfunction "DDR_DQDM7_F1") (pintype "passive"))
    )
    (net (code "45") (name "/DDR_DQ8") (class "Default")
      (node (ref "U34") (pin "E3") (pinfunction "DDR_DQDM9_E3") (pintype "passive"))
    )
    (net (code "46") (name "/DDR_DQ9") (class "Default")
      (node (ref "U34") (pin "C3") (pinfunction "DDR_DQDM10_C3") (pintype "passive"))
    )
    (net (code "47") (name "/DDR_DQ10") (class "Default")
      (node (ref "U34") (pin "D3") (pinfunction "DDR_DQDM11_D3") (pintype "passive"))
    )
    (net (code "48") (name "/DDR_DQ11") (class "Default")
      (node (ref "U34") (pin "B3") (pinfunction "DDR_DQDM12_B3") (pintype "passive"))
    )
    (net (code "49") (name "/DDR_DQ12") (class "Default")
      (node (ref "U34") (pin "D4") (pinfunction "DDR_DQDM13_D4") (pintype "passive"))
    )
    (net (code "50") (name "/DDR_DQ13") (class "Default")
      (node (ref "U34") (pin "C4") (pinfunction "DDR_DQDM14_C4") (pintype "passive"))
    )
    (net (code "51") (name "/DDR_DQ14") (class "Default")
      (node (ref "U34") (pin "B4") (pinfunction "DDR_DQDM15_B4") (pintype "passive"))
    )
    (net (code "52") (name "/DDR_DQ15") (class "Default")
      (node (ref "U34") (pin "B5") (pinfunction "DDR_DQDM16_B5") (pintype "passive"))
    )
    (net (code "53") (name "/DDR_DQ16") (class "Default")
      (node (ref "U34") (pin "E13") (pinfunction "DDR_DQDM18_E13") (pintype "passive"))
    )
    (net (code "54") (name "/DDR_DQ17") (class "Default")
      (node (ref "U34") (pin "C14") (pinfunction "DDR_DQDM19_C14") (pintype "passive"))
    )
    (net (code "55") (name "/DDR_DQ18") (class "Default")
      (node (ref "U34") (pin "B14") (pinfunction "DDR_DQDM20_B14") (pintype "passive"))
    )
    (net (code "56") (name "/DDR_DQ19") (class "Default")
      (node (ref "U34") (pin "A14") (pinfunction "DDR_DQDM21_A14") (pintype "passive"))
    )
    (net (code "57") (name "/DDR_DQ20") (class "Default")
      (node (ref "U34") (pin "E14") (pinfunction "DDR_DQDM22_E14") (pintype "passive"))
    )
    (net (code "58") (name "/DDR_DQ21") (class "Default")
      (node (ref "U34") (pin "B13") (pinfunction "DDR_DQDM23_B13") (pintype "passive"))
    )
    (net (code "59") (name "/DDR_DQ22") (class "Default")
      (node (ref "U34") (pin "C13") (pinfunction "DDR_DQDM24_C13") (pintype "passive"))
    )
    (net (code "60") (name "/DDR_DQ23") (class "Default")
      (node (ref "U34") (pin "D13") (pinfunction "DDR_DQDM25_D13") (pintype "passive"))
    )
    (net (code "61") (name "/DDR_DQ24") (class "Default")
      (node (ref "U34") (pin "D15") (pinfunction "DDR_DQDM27_D15") (pintype "passive"))
    )
    (net (code "62") (name "/DDR_DQ25") (class "Default")
      (node (ref "U34") (pin "C15") (pinfunction "DDR_DQDM28_C15") (pintype "passive"))
    )
    (net (code "63") (name "/DDR_DQ26") (class "Default")
      (node (ref "U34") (pin "E16") (pinfunction "DDR_DQDM29_E16") (pintype "passive"))
    )
    (net (code "64") (name "/DDR_DQ27") (class "Default")
      (node (ref "U34") (pin "E15") (pinfunction "DDR_DQDM30_E15") (pintype "passive"))
    )
    (net (code "65") (name "/DDR_DQ28") (class "Default")
      (node (ref "U34") (pin "D16") (pinfunction "DDR_DQDM31_D16") (pintype "passive"))
    )
    (net (code "66") (name "/DDR_DQ29") (class "Default")
      (node (ref "U34") (pin "B16") (pinfunction "DDR_DQDM32_B16") (pintype "passive"))
    )
    (net (code "67") (name "/DDR_DQ30") (class "Default")
      (node (ref "U34") (pin "C16") (pinfunction "DDR_DQDM33_C16") (pintype "passive"))
    )
    (net (code "68") (name "/DDR_DQ31") (class "Default")
      (node (ref "U34") (pin "A17") (pinfunction "DDR_DQDM34_A17") (pintype "passive"))
    )
    (net (code "69") (name "/DDR_DQ36") (class "Default")
      (node (ref "U34") (pin "B19") (pinfunction "DDR_DQDM36_B19") (pintype "passive"))
      (node (ref "U38") (pin "C2") (pinfunction "DQ0_C2") (pintype "bidirectional"))
    )
    (net (code "70") (name "/DDR_DQ37") (class "Default")
      (node (ref "U34") (pin "B18") (pinfunction "DDR_DQDM37_B18") (pintype "passive"))
      (node (ref "U38") (pin "B7") (pinfunction "DQ1_B7") (pintype "bidirectional"))
    )
    (net (code "71") (name "/DDR_DQ38") (class "Default")
      (node (ref "U34") (pin "C18") (pinfunction "DDR_DQDM38_C18") (pintype "passive"))
      (node (ref "U38") (pin "D3") (pinfunction "DQ2_D3") (pintype "bidirectional"))
    )
    (net (code "72") (name "/DDR_DQ39") (class "Default")
      (node (ref "U34") (pin "D18") (pinfunction "DDR_DQDM39_D18") (pintype "passive"))
      (node (ref "U38") (pin "D7") (pinfunction "DQ3_D7") (pintype "bidirectional"))
    )
    (net (code "73") (name "/DDR_DQ40") (class "Default")
      (node (ref "U34") (pin "E18") (pinfunction "DDR_DQDM40_E18") (pintype "passive"))
      (node (ref "U38") (pin "D2") (pinfunction "DQ4/NC_D2") (pintype "bidirectional"))
    )
    (net (code "74") (name "/DDR_DQ41") (class "Default")
      (node (ref "U34") (pin "E17") (pinfunction "DDR_DQDM41_E17") (pintype "passive"))
      (node (ref "U38") (pin "D8") (pinfunction "DQ5/NC_D8") (pintype "bidirectional"))
    )
    (net (code "75") (name "/DDR_DQ42") (class "Default")
      (node (ref "U34") (pin "D17") (pinfunction "DDR_DQDM42_D17") (pintype "passive"))
      (node (ref "U38") (pin "E3") (pinfunction "DQ6/NC_E3") (pintype "bidirectional"))
    )
    (net (code "76") (name "/DDR_DQS0_N") (class "Default")
      (node (ref "U34") (pin "C1") (pinfunction "DDR_DQS0_N_C1") (pintype "passive"))
    )
    (net (code "77") (name "/DDR_DQS0_P") (class "Default")
      (node (ref "U34") (pin "D1") (pinfunction "DDR_DQS0_D1") (pintype "passive"))
    )
    (net (code "78") (name "/DDR_DQS1_N") (class "Default")
      (node (ref "U34") (pin "A4") (pinfunction "DDR_DQS1_N_A4") (pintype "passive"))
    )
    (net (code "79") (name "/DDR_DQS1_P") (class "Default")
      (node (ref "U34") (pin "A5") (pinfunction "DDR_DQS1_A5") (pintype "passive"))
    )
    (net (code "80") (name "/DDR_DQS2_N") (class "Default")
      (node (ref "U34") (pin "A12") (pinfunction "DDR_DQS2_N_A12") (pintype "passive"))
    )
    (net (code "81") (name "/DDR_DQS2_P") (class "Default")
      (node (ref "U34") (pin "A13") (pinfunction "DDR_DQS2_A13") (pintype "passive"))
    )
    (net (code "82") (name "/DDR_DQS3_N") (class "Default")
      (node (ref "U34") (pin "A16") (pinfunction "DDR_DQS3_N_A16") (pintype "passive"))
    )
    (net (code "83") (name "/DDR_DQS3_P") (class "Default")
      (node (ref "U34") (pin "A15") (pinfunction "DDR_DQS3_A15") (pintype "passive"))
    )
    (net (code "84") (name "/DDR_DQS_N") (class "Default")
      (node (ref "U34") (pin "A18") (pinfunction "DDR_DQS4_N_A18") (pintype "passive"))
      (node (ref "U38") (pin "B3") (pinfunction "DQS_C_B3") (pintype "bidirectional"))
    )
    (net (code "85") (name "/DDR_DQS_P") (class "Default")
      (node (ref "U34") (pin "A19") (pinfunction "DDR_DQS4_A19") (pintype "passive"))
      (node (ref "U38") (pin "C3") (pinfunction "DQS_T_C3") (pintype "bidirectional"))
    )
    (net (code "91") (name "/DDR_ODT") (class "Default")
      (node (ref "R377") (pin "1") (pinfunction "1_1") (pintype "passive"))
      (node (ref "U34") (pin "B11") (pinfunction "DDR_AC25_B11") (pintype "passive"))
      (node (ref "U38") (pin "F3") (pinfunction "ODT_F3") (pintype "passive"))
    )
    (net (code "92") (name "/DDR_ODT1") (class "Default")
      (node (ref "R56") (pin "1") (pinfunction "1_1") (pintype "passive"))
      (node (ref "U34") (pin "E12") (pinfunction "DDR_AC28_E12") (pintype "passive"))
      (node (ref "U38") (pin "F2") (pinfunction "C2/ODT1_F2") (pintype "passive"))
    )
    (net (code "93") (name "/DDR_PARITY") (class "Default")
      (node (ref "R391") (pin "1") (pinfunction "1_1") (pintype "passive"))
      (node (ref "U34") (pin "B10") (pinfunction "DDR_AC23_B10") (pintype "passive"))
      (node (ref "U38") (pin "N3") (pinfunction "PAR_N3") (pintype "passive"))
    )
    (net (code "94") (name "/DDR_RESET#") (class "Default")
      (node (ref "R165") (pin "1") (pinfunction "1_1") (pintype "passive"))
      (node (ref "R171") (pin "1") (pinfunction "1_1") (pintype "passive"))
      (node (ref "R219") (pin "2") (pinfunction "2_2") (pintype "passive"))
      (node (ref "R220") (pin "1") (pinfunction "1_1") (pintype "passive"))
      (node (ref "U38") (pin "L1") (pinfunction "RESET_N_L1") (pintype "passive"))
    )
    (net (code "95") (name "/DDR_RESET_FS") (class "Default")
      (node (ref "R171") (pin "2") (pinfunction "2_2") (pintype "passive"))
      (node (ref "R182") (pin "1") (pinfunction "1_1") (pintype "passive"))
      (node (ref "U34") (pin "F16") (pinfunction "DDR_FS_RESET_N_F16") (pintype "passive"))
    )
    (net (code "96") (name "/DDR_TEN") (class "Default")
      (node (ref "R462") (pin "2") (pinfunction "2_2") (pintype "passive"))
      (node (ref "R503") (pin "1") (pinfunction "1_1") (pintype "passive"))
      (node (ref "U38") (pin "G9") (pinfunction "TEN_G9") (pintype "passive"))
    )
    (net (code "97") (name "DDR_VPP") (class "Default")
      (node (ref "C181") (pin "1") (pinfunction "1_1") (pintype "passive"))
      (node (ref "C184") (pin "1") (pinfunction "1_1") (pintype "passive"))
      (node (ref "C203") (pin "1") (pinfunction "1_1") (pintype "passive"))
      (node (ref "FL1") (pin "2") (pinfunction "2_2") (pintype "passive"))
      (node (ref "U38") (pin "B1") (pinfunction "VPP_B1") (pintype "power_in"))
      (node (ref "U38") (pin "M9") (pinfunction "VPP_M9") (pintype "power_in"))
    )
    (net (code "98") (name "DDR_VREFCA") (class "Default")
      (node (ref "C206") (pin "1") (pinfunction "1_1") (pintype "passive"))
      (node (ref "C597") (pin "1") (pinfunction "1_1") (pintype "passive"))
      (node (ref "R728") (pin "1") (pinfunction "1_1") (pintype "passive"))
      (node (ref "U38") (pin "J1") (pinfunction "VREFCA_J1") (pintype "power_in"))
    )
    (net (code "99") (name "DGND") (class "Default")
      (node (ref "C181") (pin "2") (pinfunction "2_2") (pintype "passive"))
      (node (ref "C182") (pin "2") (pinfunction "2_2") (pintype "passive"))
      (node (ref "C183") (pin "2") (pinfunction "2_2") (pintype "passive"))
      (node (ref "C184") (pin "2") (pinfunction "2_2") (pintype "passive"))
      (node (ref "C185") (pin "2") (pinfunction "2_2") (pintype "passive"))
      (node (ref "C190") (pin "2") (pinfunction "2_2") (pintype "passive"))
      (node (ref "C202") (pin "2") (pinfunction "2_2") (pintype "passive"))
      (node (ref "C203") (pin "2") (pinfunction "2_2") (pintype "passive"))
      (node (ref "C204") (pin "2") (pinfunction "2_2") (pintype "passive"))
      (node (ref "C205") (pin "2") (pinfunction "2_2") (pintype "passive"))
      (node (ref "C206") (pin "2") (pinfunction "2_2") (pintype "passive"))
      (node (ref "C207") (pin "2") (pinfunction "2_2") (pintype "passive"))
      (node (ref "C30") (pin "2") (pinfunction "2_2") (pintype "passive"))
      (node (ref "C31") (pin "2") (pinfunction "2_2") (pintype "passive"))
      (node (ref "C32") (pin "2") (pinfunction "2_2") (pintype "passive"))
      (node (ref "C328") (pin "2") (pinfunction "2_2") (pintype "passive"))
      (node (ref "C33") (pin "2") (pinfunction "2_2") (pintype "passive"))
      (node (ref "C34") (pin "2") (pinfunction "2_2") (pintype "passive"))
      (node (ref "C35") (pin "2") (pinfunction "2_2") (pintype "passive"))
      (node (ref "C36") (pin "2") (pinfunction "2_2") (pintype "passive"))
      (node (ref "C504") (pin "2") (pinfunction "2_2") (pintype "passive"))
      (node (ref "C505") (pin "2") (pinfunction "2_2") (pintype "passive"))
      (node (ref "C52") (pin "2") (pinfunction "2_2") (pintype "passive"))
      (node (ref "C57") (pin "2") (pinfunction "2_2") (pintype "passive"))
      (node (ref "C579") (pin "2") (pinfunction "2_2") (pintype "passive"))
      (node (ref "C583") (pin "2") (pinfunction "2_2") (pintype "passive"))
      (node (ref "C585") (pin "2") (pinfunction "2_2") (pintype "passive"))
      (node (ref "C593") (pin "2") (pinfunction "2_2") (pintype "passive"))
      (node (ref "C594") (pin "2") (pinfunction "2_2") (pintype "passive"))
      (node (ref "C597") (pin "2") (pinfunction "2_2") (pintype "passive"))
      (node (ref "C64") (pin "2") (pinfunction "2_2") (pintype "passive"))
      (node (ref "C65") (pin "2") (pinfunction "2_2") (pintype "passive"))
      (node (ref "C67") (pin "2") (pinfunction "2_2") (pintype "passive"))
      (node (ref "C70") (pin "2") (pinfunction "2_2") (pintype "passive"))
      (node (ref "C71") (pin "2") (pinfunction "2_2") (pintype "passive"))
      (node (ref "R186") (pin "2") (pinfunction "2_2") (pintype "passive"))
      (node (ref "R212") (pin "2") (pinfunction "2_2") (pintype "passive"))
      (node (ref "R219") (pin "1") (pinfunction "1_1") (pintype "passive"))
      (node (ref "R462") (pin "1") (pinfunction "1_1") (pintype "passive"))
      (node (ref "R730") (pin "2") (pinfunction "2_2") (pintype "passive"))
      (node (ref "R731") (pin "2") (pinfunction "2_2") (pintype "passive"))
      (node (ref "U38") (pin "A2") (pinfunction "VSSQ_A2") (pintype "power_in"))
      (node (ref "U38") (pin "A8") (pinfunction "VSSQ_A8") (pintype "power_in"))
      (node (ref "U38") (pin "A9") (pinfunction "VSS_A9") (pintype "power_in"))
      (node (ref "U38") (pin "C8") (pinfunction "VSS_C8") (pintype "power_in"))
      (node (ref "U38") (pin "D1") (pinfunction "VSSQ_D1") (pintype "power_in"))
      (node (ref "U38") (pin "D9") (pinfunction "VSSQ_D9") (pintype "power_in"))
      (node (ref "U38") (pin "E1") (pinfunction "VSS_E1") (pintype "power_in"))
      (node (ref "U38") (pin "E9") (pinfunction "VSS_E9") (pintype "power_in"))
      (node (ref "U38") (pin "G1") (pinfunction "VSS_G1") (pintype "power_in"))
      (node (ref "U38") (pin "H9") (pinfunction "VSS_H9") (pintype "power_in"))
      (node (ref "U38") (pin "K1") (pinfunction "VSS_K1") (pintype "power_in"))
      (node (ref "U38") (pin "K9") (pinfunction "VSS_K9") (pintype "power_in"))
      (node (ref "U38") (pin "N1") (pinfunction "VSS_N1") (pintype "power_in"))
    )
    (net (code "100") (name "Net-(C303-Pad2)") (class "Default")
      (node (ref "C303") (pin "2") (pinfunction "2_2") (pintype "passive"))
      (node (ref "R373") (pin "2") (pinfunction "2_2") (pintype "passive"))
      (node (ref "R374") (pin "2") (pinfunction "2_2") (pintype "passive"))
    )
    (net (code "101") (name "Net-(TP18-TP)") (class "Default")
      (node (ref "TP18") (pin "1") (pinfunction "TP_1") (pintype "passive"))
      (node (ref "U38") (pin "A3") (pinfunction "NF/NF/TDQS_C/NF_A3") (pintype "passive"))
    )
    (net (code "102") (name "Net-(TP39-TP)") (class "Default")
      (node (ref "TP39") (pin "1") (pinfunction "TP_1") (pintype "passive"))
      (node (ref "U34") (pin "B7") (pinfunction "DDR_CK1_N_B7") (pintype "passive"))
    )
    (net (code "103") (name "Net-(TP41-TP)") (class "Default")
      (node (ref "TP41") (pin "1") (pinfunction "TP_1") (pintype "passive"))
      (node (ref "U34") (pin "A7") (pinfunction "DDR_CK1_A7") (pintype "passive"))
    )
    (net (code "104") (name "Net-(TP42-TP)") (class "Default")
      (node (ref "TP42") (pin "1") (pinfunction "TP_1") (pintype "passive"))
      (node (ref "U34") (pin "F9") (pinfunction "DDR_DTESTOUT0_F9") (pintype "passive"))
    )
    (net (code "105") (name "Net-(TP44-TP)") (class "Default")
      (node (ref "TP44") (pin "1") (pinfunction "TP_1") (pintype "passive"))
      (node (ref "U34") (pin "F10") (pinfunction "DDR_DTESTOUT1_F10") (pintype "passive"))
    )
    (net (code "106") (name "Net-(TP45-TP)") (class "Default")
      (node (ref "TP45") (pin "1") (pinfunction "TP_1") (pintype "passive"))
      (node (ref "U34") (pin "C12") (pinfunction "DDR_ATESTOUTO_C12") (pintype "passive"))
    )
    (net (code "107") (name "Net-(TP46-TP)") (class "Default")
      (node (ref "TP46") (pin "1") (pinfunction "TP_1") (pintype "passive"))
      (node (ref "U34") (pin "F15") (pinfunction "DDR_VREF_ZQ_F15") (pintype "passive"))
    )
    (net (code "108") (name "Net-(U34O-DDR_RESET_N)") (class "Default")
      (node (ref "R165") (pin "2") (pinfunction "2_2") (pintype "passive"))
      (node (ref "U34") (pin "A11") (pinfunction "DDR_RESET_N_A11") (pintype "passive"))
    )
    (net (code "109") (name "Net-(U34O-DDR_VTP)") (class "Default")
      (node (ref "R186") (pin "1") (pinfunction "1_1") (pintype "passive"))
      (node (ref "U34") (pin "F13") (pinfunction "DDR_VTP_F13") (pintype "passive"))
    )
    (net (code "110") (name "Net-(U38-DQ7{slash}NC)") (class "Default")
      (node (ref "R516") (pin "2") (pinfunction "2_2") (pintype "passive"))
      (node (ref "U38") (pin "E7") (pinfunction "DQ7/NC_E7") (pintype "bidirectional"))
    )
    (net (code "111") (name "Net-(U38-ZQ)") (class "Default")
      (node (ref "R212") (pin "1") (pinfunction "1_1") (pintype "passive"))
      (node (ref "U38") (pin "B9") (pinfunction "ZQ_B9") (pintype "passive"))
    )
    (net (code "112") (name "SoC_DDR_VREFCA") (class "Default")
      (node (ref "C504") (pin "1") (pinfunction "1_1") (pintype "passive"))
      (node (ref "C505") (pin "1") (pinfunction "1_1") (pintype "passive"))
      (node (ref "R728") (pin "2") (pinfunction "2_2") (pintype "passive"))
      (node (ref "U34") (pin "F12") (pinfunction "DDR_VREF0_F12") (pintype "passive"))
    )
    (net (code "113") (name "VCC_2V5") (class "Default")
      (node (ref "FL1") (pin "1") (pinfunction "1_1") (pintype "passive"))
    )
    (net (code "114") (name "VDDR_VTT") (class "Default")
      (node (ref "C30") (pin "1") (pinfunction "1_1") (pintype "passive"))
      (node (ref "C31") (pin "1") (pinfunction "1_1") (pintype "passive"))
      (node (ref "C32") (pin "1") (pinfunction "1_1") (pintype "passive"))
      (node (ref "C328") (pin "1") (pinfunction "1_1") (pintype "passive"))
      (node (ref "C33") (pin "1") (pinfunction "1_1") (pintype "passive"))
      (node (ref "C34") (pin "1") (pinfunction "1_1") (pintype "passive"))
      (node (ref "C35") (pin "1") (pinfunction "1_1") (pintype "passive"))
      (node (ref "C36") (pin "1") (pinfunction "1_1") (pintype "passive"))
      (node (ref "C52") (pin "1") (pinfunction "1_1") (pintype "passive"))
      (node (ref "C57") (pin "1") (pinfunction "1_1") (pintype "passive"))
      (node (ref "C64") (pin "1") (pinfunction "1_1") (pintype "passive"))
      (node (ref "C65") (pin "1") (pinfunction "1_1") (pintype "passive"))
      (node (ref "C67") (pin "1") (pinfunction "1_1") (pintype "passive"))
      (node (ref "C70") (pin "1") (pinfunction "1_1") (pintype "passive"))
      (node (ref "C71") (pin "1") (pinfunction "1_1") (pintype "passive"))
      (node (ref "R366") (pin "2") (pinfunction "2_2") (pintype "passive"))
      (node (ref "R367") (pin "2") (pinfunction "2_2") (pintype "passive"))
      (node (ref "R368") (pin "2") (pinfunction "2_2") (pintype "passive"))
      (node (ref "R369") (pin "2") (pinfunction "2_2") (pintype "passive"))
      (node (ref "R370") (pin "2") (pinfunction "2_2") (pintype "passive"))
      (node (ref "R371") (pin "2") (pinfunction "2_2") (pintype "passive"))
      (node (ref "R372") (pin "2") (pinfunction "2_2") (pintype "passive"))
      (node (ref "R377") (pin "2") (pinfunction "2_2") (pintype "passive"))
      (node (ref "R379") (pin "2") (pinfunction "2_2") (pintype "passive"))
      (node (ref "R382") (pin "2") (pinfunction "2_2") (pintype "passive"))
      (node (ref "R383") (pin "2") (pinfunction "2_2") (pintype "passive"))
      (node (ref "R386") (pin "2") (pinfunction "2_2") (pintype "passive"))
      (node (ref "R389") (pin "2") (pinfunction "2_2") (pintype "passive"))
      (node (ref "R391") (pin "2") (pinfunction "2_2") (pintype "passive"))
      (node (ref "R393") (pin "2") (pinfunction "2_2") (pintype "passive"))
      (node (ref "R43") (pin "2") (pinfunction "2_2") (pintype "passive"))
      (node (ref "R44") (pin "2") (pinfunction "2_2") (pintype "passive"))
      (node (ref "R45") (pin "2") (pinfunction "2_2") (pintype "passive"))
      (node (ref "R46") (pin "2") (pinfunction "2_2") (pintype "passive"))
      (node (ref "R47") (pin "2") (pinfunction "2_2") (pintype "passive"))
      (node (ref "R48") (pin "2") (pinfunction "2_2") (pintype "passive"))
      (node (ref "R49") (pin "2") (pinfunction "2_2") (pintype "passive"))
      (node (ref "R56") (pin "2") (pinfunction "2_2") (pintype "passive"))
      (node (ref "R57") (pin "2") (pinfunction "2_2") (pintype "passive"))
      (node (ref "R61") (pin "2") (pinfunction "2_2") (pintype "passive"))
      (node (ref "R63") (pin "2") (pinfunction "2_2") (pintype "passive"))
      (node (ref "R67") (pin "2") (pinfunction "2_2") (pintype "passive"))
      (node (ref "R69") (pin "2") (pinfunction "2_2") (pintype "passive"))
      (node (ref "R70") (pin "2") (pinfunction "2_2") (pintype "passive"))
      (node (ref "R742") (pin "2") (pinfunction "2_2") (pintype "passive"))
    )
    (net (code "115") (name "VDD_DDR4") (class "Default")
      (node (ref "C182") (pin "1") (pinfunction "1_1") (pintype "passive"))
      (node (ref "C183") (pin "1") (pinfunction "1_1") (pintype "passive"))
      (node (ref "C185") (pin "1") (pinfunction "1_1") (pintype "passive"))
      (node (ref "C190") (pin "1") (pinfunction "1_1") (pintype "passive"))
      (node (ref "C202") (pin "1") (pinfunction "1_1") (pintype "passive"))
      (node (ref "C204") (pin "1") (pinfunction "1_1") (pintype "passive"))
      (node (ref "C205") (pin "1") (pinfunction "1_1") (pintype "passive"))
      (node (ref "C207") (pin "1") (pinfunction "1_1") (pintype "passive"))
      (node (ref "C303") (pin "1") (pinfunction "1_1") (pintype "passive"))
      (node (ref "C579") (pin "1") (pinfunction "1_1") (pintype "passive"))
      (node (ref "C583") (pin "1") (pinfunction "1_1") (pintype "passive"))
      (node (ref "C585") (pin "1") (pinfunction "1_1") (pintype "passive"))
      (node (ref "C593") (pin "1") (pinfunction "1_1") (pintype "passive"))
      (node (ref "C594") (pin "1") (pinfunction "1_1") (pintype "passive"))
      (node (ref "R182") (pin "2") (pinfunction "2_2") (pintype "passive"))
      (node (ref "R220") (pin "2") (pinfunction "2_2") (pintype "passive"))
      (node (ref "R460") (pin "2") (pinfunction "2_2") (pintype "passive"))
      (node (ref "R503") (pin "2") (pinfunction "2_2") (pintype "passive"))
      (node (ref "R516") (pin "1") (pinfunction "1_1") (pintype "passive"))
      (node (ref "U38") (pin "A1") (pinfunction "VDD_A1") (pintype "power_in"))
      (node (ref "U38") (pin "B2") (pinfunction "VDDQ_B2") (pintype "power_in"))
      (node (ref "U38") (pin "B8") (pinfunction "VDDQ_B8") (pintype "power_in"))
      (node (ref "U38") (pin "C1") (pinfunction "VDDQ_C1") (pintype "power_in"))
      (node (ref "U38") (pin "C7") (pinfunction "VDD_C7") (pintype "power_in"))
      (node (ref "U38") (pin "C9") (pinfunction "VDDQ_C9") (pintype "power_in"))
      (node (ref "U38") (pin "E2") (pinfunction "VDDQ_E2") (pintype "power_in"))
      (node (ref "U38") (pin "E8") (pinfunction "VDDQ_E8") (pintype "power_in"))
      (node (ref "U38") (pin "F1") (pinfunction "VDD_F1") (pintype "power_in"))
      (node (ref "U38") (pin "F9") (pinfunction "VDD_F9") (pintype "power_in"))
      (node (ref "U38") (pin "H1") (pinfunction "VDD_H1") (pintype "power_in"))
      (node (ref "U38") (pin "J9") (pinfunction "VDD_J9") (pintype "power_in"))
      (node (ref "U38") (pin "M1") (pinfunction "VDD_M1") (pintype "power_in"))
      (node (ref "U38") (pin "N9") (pinfunction "VDD_N9") (pintype "power_in"))
    )
  )
)
